# ErikSpark_AtTiny85.net
KiCad netlist of a schematic drawn in EAGLE
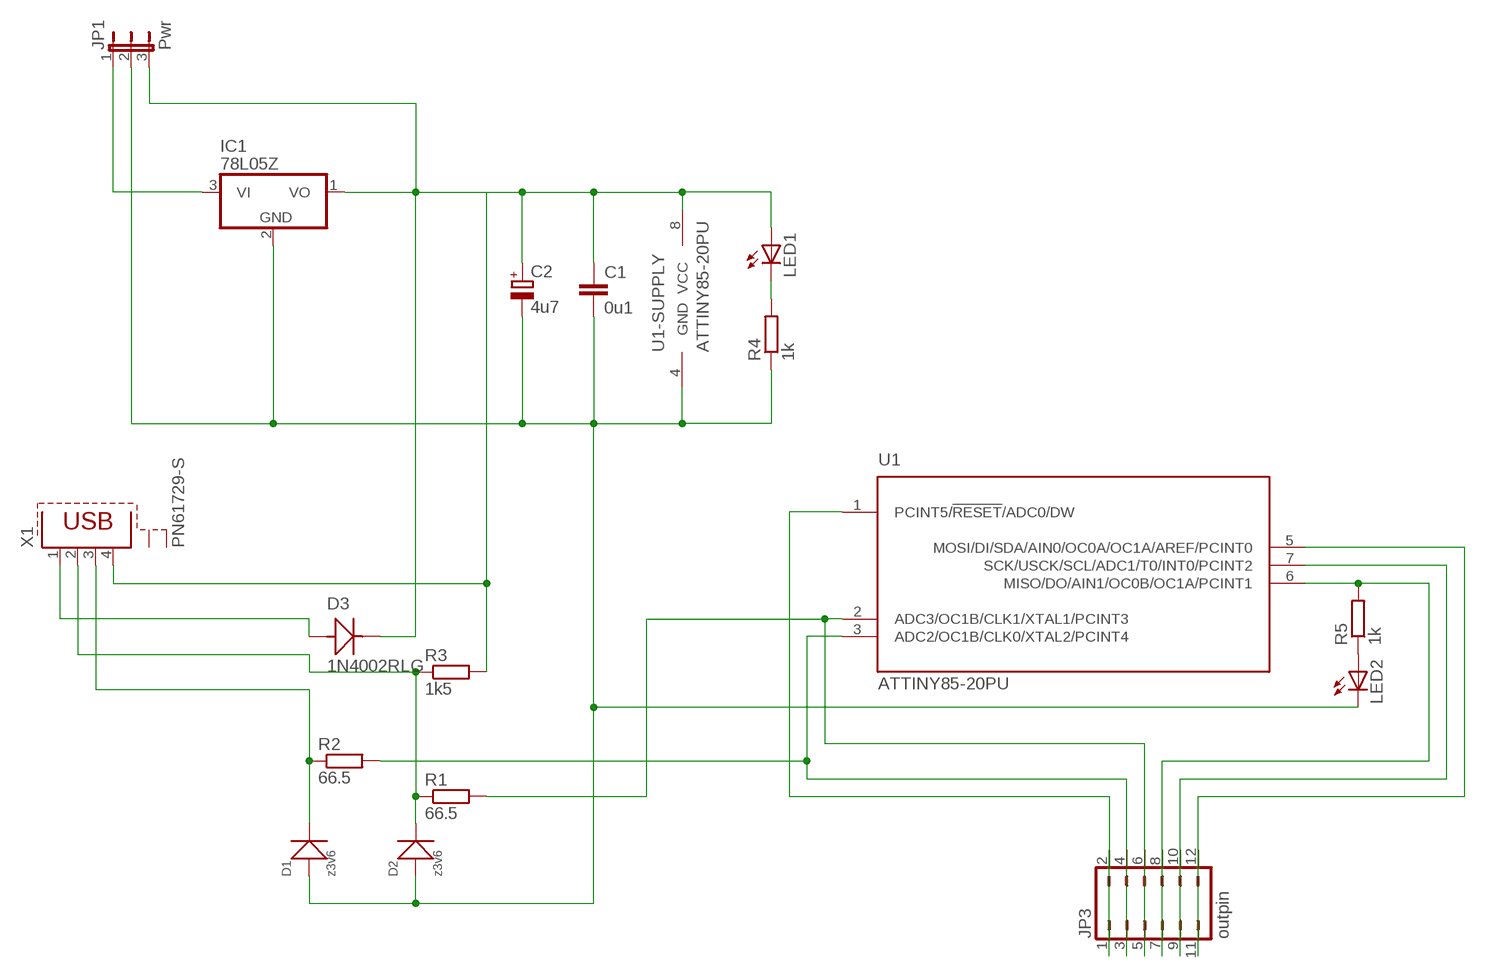
[diagram p0: schematic, sheet 1]

(export (version "E")
  (design (tool "Eeschema 10.0.6"))
  (components
    (comp (ref "C1")
      (value "0u1")
      (footprint "eagle-import:C050-024X044")
      (libsource (lib "eagle-import") (part "C-EU050-024X044"))
    )
    (comp (ref "C2")
      (value "4u7")
      (footprint "eagle-import:E2-4")
      (libsource (lib "eagle-import") (part "CPOL-EUE2-4"))
    )
    (comp (ref "D1")
      (value "z3v6")
      (footprint "eagle-import:DO-35")
      (fields (field (name "MPN") "1N5227B"))
      (libsource (lib "eagle-import") (part "DIP-DIODE-ZENER-3.6V-500MW(DO-35)"))
    )
    (comp (ref "D2")
      (value "z3v6")
      (footprint "eagle-import:DO-35")
      (fields (field (name "MPN") "1N5227B"))
      (libsource (lib "eagle-import") (part "DIP-DIODE-ZENER-3.6V-500MW(DO-35)"))
    )
    (comp (ref "D3")
      (value "1N4002RLG")
      (footprint "eagle-import:DO-41")
      (fields (field (name "MANUFACTURER") "ON Semiconductor"))
      (libsource (lib "eagle-import") (part "1N?G4002RL"))
    )
    (comp (ref "IC1")
      (value "78L05Z")
      (footprint "eagle-import:TO92")
      (libsource (lib "eagle-import") (part "78ZL05"))
    )
    (comp (ref "JP1")
      (value "Pwr")
      (footprint "eagle-import:JP2")
      (libsource (lib "eagle-import") (part "JP2E"))
    )
    (comp (ref "JP3")
      (value "outpin")
      (footprint "eagle-import:JP6Q")
      (libsource (lib "eagle-import") (part "JP6Q"))
    )
    (comp (ref "LED1")
      (value "LED3MM")
      (footprint "eagle-import:LED3MM")
      (libsource (lib "eagle-import") (part "LED3MM"))
    )
    (comp (ref "LED2")
      (value "LED3MM")
      (footprint "eagle-import:LED3MM")
      (libsource (lib "eagle-import") (part "LED3MM"))
    )
    (comp (ref "R1")
      (value "66.5")
      (footprint "eagle-import:0207_15")
      (libsource (lib "eagle-import") (part "R-EU_0207/15"))
    )
    (comp (ref "R2")
      (value "66.5")
      (footprint "eagle-import:0207_15")
      (libsource (lib "eagle-import") (part "R-EU_0207/15"))
    )
    (comp (ref "R3")
      (value "1k5")
      (footprint "eagle-import:0207_15")
      (libsource (lib "eagle-import") (part "R-EU_0207/15"))
    )
    (comp (ref "R4")
      (value "1k")
      (footprint "eagle-import:0207_15")
      (libsource (lib "eagle-import") (part "R-EU_0207/15"))
    )
    (comp (ref "R5")
      (value "1k")
      (footprint "eagle-import:0207_15")
      (libsource (lib "eagle-import") (part "R-EU_0207/15"))
    )
    (comp (ref "U1")
      (value "ATTINY85-20PU")
      (footprint "eagle-import:DIP-8")
      (fields (field (name "MANUFACTURER") "Atmel"))
      (libsource (lib "eagle-import") (part "ATTINY5-?20PU8"))
    )
    (comp (ref "X1")
      (value "PN61729-S")
      (footprint "eagle-import:PN61729-S")
      (libsource (lib "eagle-import") (part "PN61729-S"))
    )
  )
  (nets
    (net (code "1") (name "Net-(D1-+)") (class "Default")
      (node (ref "C1") (pin "2") (pinfunction "2_2") (pintype "passive"))
      (node (ref "C2") (pin "-") (pinfunction "-_-") (pintype "passive"))
      (node (ref "D1") (pin "A") (pinfunction "+_A") (pintype "passive"))
      (node (ref "D2") (pin "A") (pinfunction "+_A") (pintype "passive"))
      (node (ref "IC1") (pin "2") (pinfunction "GND_2") (pintype "passive"))
      (node (ref "JP1") (pin "2") (pinfunction "2_2") (pintype "passive"))
      (node (ref "LED2") (pin "K") (pinfunction "C_K") (pintype "passive"))
      (node (ref "R4") (pin "1") (pinfunction "1_1") (pintype "passive"))
      (node (ref "U1") (pin "4") (pinfunction "GND_4") (pintype "power_in"))
    )
    (net (code "2") (name "Net-(D1--)") (class "Default")
      (node (ref "D1") (pin "C") (pinfunction "-_C") (pintype "passive"))
      (node (ref "R2") (pin "1") (pinfunction "1_1") (pintype "passive"))
      (node (ref "X1") (pin "3") (pinfunction "3_3") (pintype "passive"))
    )
    (net (code "3") (name "Net-(D2--)") (class "Default")
      (node (ref "D2") (pin "C") (pinfunction "-_C") (pintype "passive"))
      (node (ref "R1") (pin "1") (pinfunction "1_1") (pintype "passive"))
      (node (ref "R3") (pin "1") (pinfunction "1_1") (pintype "passive"))
      (node (ref "X1") (pin "2") (pinfunction "2_2") (pintype "passive"))
    )
    (net (code "4") (name "Net-(D3-PadA)") (class "Default")
      (node (ref "D3") (pin "A") (pinfunction "A_A") (pintype "passive"))
      (node (ref "X1") (pin "1") (pinfunction "1_1") (pintype "passive"))
    )
    (net (code "5") (name "Net-(IC1-VI)") (class "Default")
      (node (ref "IC1") (pin "3") (pinfunction "VI_3") (pintype "input"))
      (node (ref "JP1") (pin "1") (pinfunction "1_1") (pintype "passive"))
    )
    (net (code "6") (name "Net-(IC1-VO)") (class "Default")
      (node (ref "C1") (pin "1") (pinfunction "1_1") (pintype "passive"))
      (node (ref "C2") (pin "+") (pinfunction "+_+") (pintype "passive"))
      (node (ref "D3") (pin "C") (pinfunction "C_C") (pintype "passive"))
      (node (ref "IC1") (pin "1") (pinfunction "VO_1") (pintype "passive"))
      (node (ref "JP1") (pin "3") (pinfunction "3_3") (pintype "passive"))
      (node (ref "LED1") (pin "A") (pinfunction "A_A") (pintype "passive"))
      (node (ref "R3") (pin "2") (pinfunction "2_2") (pintype "passive"))
      (node (ref "U1") (pin "8") (pinfunction "VCC_8") (pintype "power_in"))
      (node (ref "X1") (pin "4") (pinfunction "4_4") (pintype "passive"))
    )
    (net (code "7") (name "Net-(LED1-C)") (class "Default")
      (node (ref "LED1") (pin "K") (pinfunction "C_K") (pintype "passive"))
      (node (ref "R4") (pin "2") (pinfunction "2_2") (pintype "passive"))
    )
    (net (code "8") (name "Net-(LED2-PadA)") (class "Default")
      (node (ref "LED2") (pin "A") (pinfunction "A_A") (pintype "passive"))
      (node (ref "R5") (pin "1") (pinfunction "1_1") (pintype "passive"))
    )
    (net (code "9") (name "Net-(U1B-ADC2{slash}OC1B{slash}CLK0{slash}XTAL2{slash}PCINT4)") (class "Default")
      (node (ref "JP3") (pin "3") (pinfunction "3_3") (pintype "passive"))
      (node (ref "JP3") (pin "4") (pinfunction "4_4") (pintype "passive"))
      (node (ref "R2") (pin "2") (pinfunction "2_2") (pintype "passive"))
      (node (ref "U1") (pin "3") (pinfunction "ADC2/OC1B/CLK0/XTAL2/PCINT4_3") (pintype "bidirectional"))
    )
    (net (code "10") (name "Net-(U1B-ADC3{slash}OC1B{slash}CLK1{slash}XTAL1{slash}PCINT3)") (class "Default")
      (node (ref "JP3") (pin "5") (pinfunction "5_5") (pintype "passive"))
      (node (ref "JP3") (pin "6") (pinfunction "6_6") (pintype "passive"))
      (node (ref "R1") (pin "2") (pinfunction "2_2") (pintype "passive"))
      (node (ref "U1") (pin "2") (pinfunction "ADC3/OC1B/CLK1/XTAL1/PCINT3_2") (pintype "bidirectional"))
    )
    (net (code "11") (name "Net-(U1B-MISO{slash}DO{slash}AIN1{slash}OC0B{slash}OC1A{slash}PCINT1)") (class "Default")
      (node (ref "JP3") (pin "7") (pinfunction "7_7") (pintype "passive"))
      (node (ref "JP3") (pin "8") (pinfunction "8_8") (pintype "passive"))
      (node (ref "R5") (pin "2") (pinfunction "2_2") (pintype "passive"))
      (node (ref "U1") (pin "6") (pinfunction "MISO/DO/AIN1/OC0B/OC1A/PCINT1_6") (pintype "bidirectional"))
    )
    (net (code "12") (name "Net-(U1B-MOSI{slash}DI{slash}SDA{slash}AIN0{slash}OC0A{slash}OC1A{slash}AREF{slash}PCINT0)") (class "Default")
      (node (ref "JP3") (pin "11") (pinfunction "11_11") (pintype "passive"))
      (node (ref "JP3") (pin "12") (pinfunction "12_12") (pintype "passive"))
      (node (ref "U1") (pin "5") (pinfunction "MOSI/DI/SDA/AIN0/OC0A/OC1A/AREF/PCINT0_5") (pintype "bidirectional"))
    )
    (net (code "13") (name "Net-(U1B-PCINT5{slash}~{RESET}{slash}ADC0{slash}DW)") (class "Default")
      (node (ref "JP3") (pin "1") (pinfunction "1_1") (pintype "passive"))
      (node (ref "JP3") (pin "2") (pinfunction "2_2") (pintype "passive"))
      (node (ref "U1") (pin "1") (pinfunction "PCINT5/~{RESET}/ADC0/DW_1") (pintype "bidirectional"))
    )
    (net (code "14") (name "Net-(U1B-SCK{slash}USCK{slash}SCL{slash}ADC1{slash}T0{slash}INT0{slash}PCINT2)") (class "Default")
      (node (ref "JP3") (pin "10") (pinfunction "10_10") (pintype "passive"))
      (node (ref "JP3") (pin "9") (pinfunction "9_9") (pintype "passive"))
      (node (ref "U1") (pin "7") (pinfunction "SCK/USCK/SCL/ADC1/T0/INT0/PCINT2_7") (pintype "bidirectional"))
    )
    (net (code "15") (name "unconnected-(X1-PadS1)") (class "Default")
      (node (ref "X1") (pin "S1") (pinfunction "S1_S1") (pintype "passive"))
    )
    (net (code "16") (name "unconnected-(X1-PadS2)") (class "Default")
      (node (ref "X1") (pin "S2") (pinfunction "S2_S2") (pintype "passive"))
    )
  )
)
